# Planks_Rev2.net
KiCad netlist of a schematic drawn in EAGLE
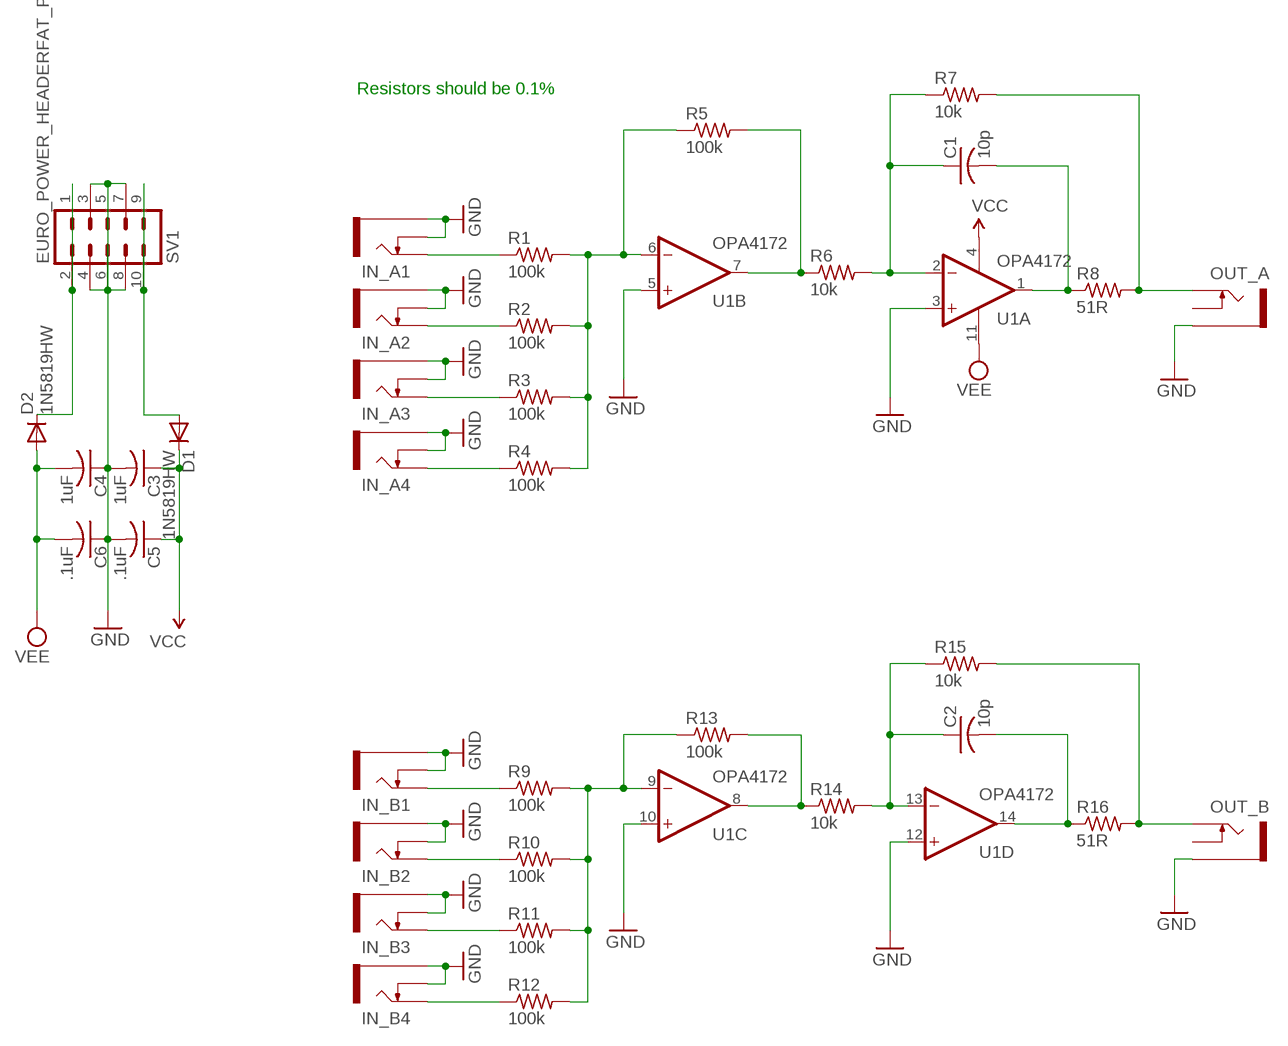
[diagram p0: schematic, sheet 1]

(export (version "E")
  (design (tool "Eeschema 10.0.6"))
  (components
    (comp (ref "C1")
      (value "10p")
      (footprint "eagle-import:C0603")
      (libsource (lib "eagle-import") (part "C-USC0603"))
    )
    (comp (ref "C2")
      (value "10p")
      (footprint "eagle-import:C0603")
      (libsource (lib "eagle-import") (part "C-USC0603"))
    )
    (comp (ref "C3")
      (value "1uF")
      (footprint "eagle-import:C0805")
      (libsource (lib "eagle-import") (part "C-USC0805"))
    )
    (comp (ref "C4")
      (value "1uF")
      (footprint "eagle-import:C0805")
      (libsource (lib "eagle-import") (part "C-USC0805"))
    )
    (comp (ref "C5")
      (value ".1uF")
      (footprint "eagle-import:C0603")
      (libsource (lib "eagle-import") (part "C-USC0603"))
    )
    (comp (ref "C6")
      (value ".1uF")
      (footprint "eagle-import:C0603")
      (libsource (lib "eagle-import") (part "C-USC0603"))
    )
    (comp (ref "D1")
      (value "1N5819HW")
      (footprint "eagle-import:SOD123")
      (libsource (lib "eagle-import") (part "DIODE-SOD123"))
    )
    (comp (ref "D2")
      (value "1N5819HW")
      (footprint "eagle-import:SOD123")
      (libsource (lib "eagle-import") (part "DIODE-SOD123"))
    )
    (comp (ref "IN_A1")
      (value "THONKICONNNEW")
      (footprint "eagle-import:WQP-PJ301M-12_JACK")
      (libsource (lib "eagle-import") (part "THONKICONNNEW"))
    )
    (comp (ref "IN_A2")
      (value "THONKICONNNEW")
      (footprint "eagle-import:WQP-PJ301M-12_JACK")
      (libsource (lib "eagle-import") (part "THONKICONNNEW"))
    )
    (comp (ref "IN_A3")
      (value "THONKICONNNEW")
      (footprint "eagle-import:WQP-PJ301M-12_JACK")
      (libsource (lib "eagle-import") (part "THONKICONNNEW"))
    )
    (comp (ref "IN_A4")
      (value "THONKICONNNEW")
      (footprint "eagle-import:WQP-PJ301M-12_JACK")
      (libsource (lib "eagle-import") (part "THONKICONNNEW"))
    )
    (comp (ref "IN_B1")
      (value "THONKICONNNEW")
      (footprint "eagle-import:WQP-PJ301M-12_JACK")
      (libsource (lib "eagle-import") (part "THONKICONNNEW"))
    )
    (comp (ref "IN_B2")
      (value "THONKICONNNEW")
      (footprint "eagle-import:WQP-PJ301M-12_JACK")
      (libsource (lib "eagle-import") (part "THONKICONNNEW"))
    )
    (comp (ref "IN_B3")
      (value "THONKICONNNEW")
      (footprint "eagle-import:WQP-PJ301M-12_JACK")
      (libsource (lib "eagle-import") (part "THONKICONNNEW"))
    )
    (comp (ref "IN_B4")
      (value "THONKICONNNEW")
      (footprint "eagle-import:WQP-PJ301M-12_JACK")
      (libsource (lib "eagle-import") (part "THONKICONNNEW"))
    )
    (comp (ref "OUT_A")
      (value "THONKICONNNEW")
      (footprint "eagle-import:WQP-PJ301M-12_JACK")
      (libsource (lib "eagle-import") (part "THONKICONNNEW"))
    )
    (comp (ref "OUT_B")
      (value "THONKICONNNEW")
      (footprint "eagle-import:WQP-PJ301M-12_JACK")
      (libsource (lib "eagle-import") (part "THONKICONNNEW"))
    )
    (comp (ref "R1")
      (value "100k")
      (footprint "eagle-import:R0603")
      (libsource (lib "eagle-import") (part "R-US_R0603"))
    )
    (comp (ref "R2")
      (value "100k")
      (footprint "eagle-import:R0603")
      (libsource (lib "eagle-import") (part "R-US_R0603"))
    )
    (comp (ref "R3")
      (value "100k")
      (footprint "eagle-import:R0603")
      (libsource (lib "eagle-import") (part "R-US_R0603"))
    )
    (comp (ref "R4")
      (value "100k")
      (footprint "eagle-import:R0603")
      (libsource (lib "eagle-import") (part "R-US_R0603"))
    )
    (comp (ref "R5")
      (value "100k")
      (footprint "eagle-import:R0603")
      (libsource (lib "eagle-import") (part "R-US_R0603"))
    )
    (comp (ref "R6")
      (value "10k")
      (footprint "eagle-import:R0603")
      (libsource (lib "eagle-import") (part "R-US_R0603"))
    )
    (comp (ref "R7")
      (value "10k")
      (footprint "eagle-import:R0603")
      (libsource (lib "eagle-import") (part "R-US_R0603"))
    )
    (comp (ref "R8")
      (value "51R")
      (footprint "eagle-import:R0603")
      (libsource (lib "eagle-import") (part "R-US_R0603"))
    )
    (comp (ref "R9")
      (value "100k")
      (footprint "eagle-import:R0603")
      (libsource (lib "eagle-import") (part "R-US_R0603"))
    )
    (comp (ref "R10")
      (value "100k")
      (footprint "eagle-import:R0603")
      (libsource (lib "eagle-import") (part "R-US_R0603"))
    )
    (comp (ref "R11")
      (value "100k")
      (footprint "eagle-import:R0603")
      (libsource (lib "eagle-import") (part "R-US_R0603"))
    )
    (comp (ref "R12")
      (value "100k")
      (footprint "eagle-import:R0603")
      (libsource (lib "eagle-import") (part "R-US_R0603"))
    )
    (comp (ref "R13")
      (value "100k")
      (footprint "eagle-import:R0603")
      (libsource (lib "eagle-import") (part "R-US_R0603"))
    )
    (comp (ref "R14")
      (value "10k")
      (footprint "eagle-import:R0603")
      (libsource (lib "eagle-import") (part "R-US_R0603"))
    )
    (comp (ref "R15")
      (value "10k")
      (footprint "eagle-import:R0603")
      (libsource (lib "eagle-import") (part "R-US_R0603"))
    )
    (comp (ref "R16")
      (value "51R")
      (footprint "eagle-import:R0603")
      (libsource (lib "eagle-import") (part "R-US_R0603"))
    )
    (comp (ref "SV1")
      (value "EURO_POWER_HEADERFAT_PADS")
      (footprint "eagle-import:EURO_PWR_HEADER_FAT")
      (libsource (lib "eagle-import") (part "EURO_POWER_HEADERFAT_PADS"))
    )
    (comp (ref "U1")
      (value "OPA4172")
      (footprint "eagle-import:SO14")
      (libsource (lib "eagle-import") (part "TL074_SMD"))
    )
  )
  (nets
    (net (code "1") (name "GND") (class "Default")
      (node (ref "C3") (pin "2") (pinfunction "2_2") (pintype "passive"))
      (node (ref "C4") (pin "1") (pinfunction "1_1") (pintype "passive"))
      (node (ref "C5") (pin "2") (pinfunction "2_2") (pintype "passive"))
      (node (ref "C6") (pin "1") (pinfunction "1_1") (pintype "passive"))
      (node (ref "IN_A1") (pin "P$2_SWITCH") (pinfunction "SWITCH_P$2_SWITCH") (pintype "passive"))
      (node (ref "IN_A1") (pin "P$3_SLEEVE") (pinfunction "SLEEVE_P$3_SLEEVE") (pintype "passive"))
      (node (ref "IN_A2") (pin "P$2_SWITCH") (pinfunction "SWITCH_P$2_SWITCH") (pintype "passive"))
      (node (ref "IN_A2") (pin "P$3_SLEEVE") (pinfunction "SLEEVE_P$3_SLEEVE") (pintype "passive"))
      (node (ref "IN_A3") (pin "P$2_SWITCH") (pinfunction "SWITCH_P$2_SWITCH") (pintype "passive"))
      (node (ref "IN_A3") (pin "P$3_SLEEVE") (pinfunction "SLEEVE_P$3_SLEEVE") (pintype "passive"))
      (node (ref "IN_A4") (pin "P$2_SWITCH") (pinfunction "SWITCH_P$2_SWITCH") (pintype "passive"))
      (node (ref "IN_A4") (pin "P$3_SLEEVE") (pinfunction "SLEEVE_P$3_SLEEVE") (pintype "passive"))
      (node (ref "IN_B1") (pin "P$2_SWITCH") (pinfunction "SWITCH_P$2_SWITCH") (pintype "passive"))
      (node (ref "IN_B1") (pin "P$3_SLEEVE") (pinfunction "SLEEVE_P$3_SLEEVE") (pintype "passive"))
      (node (ref "IN_B2") (pin "P$2_SWITCH") (pinfunction "SWITCH_P$2_SWITCH") (pintype "passive"))
      (node (ref "IN_B2") (pin "P$3_SLEEVE") (pinfunction "SLEEVE_P$3_SLEEVE") (pintype "passive"))
      (node (ref "IN_B3") (pin "P$2_SWITCH") (pinfunction "SWITCH_P$2_SWITCH") (pintype "passive"))
      (node (ref "IN_B3") (pin "P$3_SLEEVE") (pinfunction "SLEEVE_P$3_SLEEVE") (pintype "passive"))
      (node (ref "IN_B4") (pin "P$2_SWITCH") (pinfunction "SWITCH_P$2_SWITCH") (pintype "passive"))
      (node (ref "IN_B4") (pin "P$3_SLEEVE") (pinfunction "SLEEVE_P$3_SLEEVE") (pintype "passive"))
      (node (ref "OUT_A") (pin "P$3_SLEEVE") (pinfunction "SLEEVE_P$3_SLEEVE") (pintype "passive"))
      (node (ref "OUT_B") (pin "P$3_SLEEVE") (pinfunction "SLEEVE_P$3_SLEEVE") (pintype "passive"))
      (node (ref "SV1") (pin "3") (pinfunction "3_3") (pintype "passive"))
      (node (ref "SV1") (pin "4") (pinfunction "4_4") (pintype "passive"))
      (node (ref "SV1") (pin "5") (pinfunction "5_5") (pintype "passive"))
      (node (ref "SV1") (pin "6") (pinfunction "6_6") (pintype "passive"))
      (node (ref "SV1") (pin "7") (pinfunction "7_7") (pintype "passive"))
      (node (ref "SV1") (pin "8") (pinfunction "8_8") (pintype "passive"))
      (node (ref "U1") (pin "10") (pinfunction "+IN_10") (pintype "input"))
      (node (ref "U1") (pin "12") (pinfunction "+IN_12") (pintype "input"))
      (node (ref "U1") (pin "3") (pinfunction "+IN_3") (pintype "input"))
      (node (ref "U1") (pin "5") (pinfunction "+IN_5") (pintype "input"))
    )
    (net (code "2") (name "Net-(D1-PadA)") (class "Default")
      (node (ref "D1") (pin "A") (pinfunction "A_A") (pintype "passive"))
      (node (ref "SV1") (pin "10") (pinfunction "10_10") (pintype "passive"))
      (node (ref "SV1") (pin "9") (pinfunction "9_9") (pintype "passive"))
    )
    (net (code "3") (name "Net-(D2-PadC)") (class "Default")
      (node (ref "D2") (pin "C") (pinfunction "C_C") (pintype "passive"))
      (node (ref "SV1") (pin "1") (pinfunction "1_1") (pintype "passive"))
      (node (ref "SV1") (pin "2") (pinfunction "2_2") (pintype "passive"))
    )
    (net (code "4") (name "Net-(IN_A1-TIP)") (class "Default")
      (node (ref "IN_A1") (pin "P$1_TIP") (pinfunction "TIP_P$1_TIP") (pintype "passive"))
      (node (ref "R1") (pin "1") (pinfunction "1_1") (pintype "passive"))
    )
    (net (code "5") (name "Net-(IN_A2-TIP)") (class "Default")
      (node (ref "IN_A2") (pin "P$1_TIP") (pinfunction "TIP_P$1_TIP") (pintype "passive"))
      (node (ref "R2") (pin "1") (pinfunction "1_1") (pintype "passive"))
    )
    (net (code "6") (name "Net-(IN_A3-TIP)") (class "Default")
      (node (ref "IN_A3") (pin "P$1_TIP") (pinfunction "TIP_P$1_TIP") (pintype "passive"))
      (node (ref "R3") (pin "1") (pinfunction "1_1") (pintype "passive"))
    )
    (net (code "7") (name "Net-(IN_A4-TIP)") (class "Default")
      (node (ref "IN_A4") (pin "P$1_TIP") (pinfunction "TIP_P$1_TIP") (pintype "passive"))
      (node (ref "R4") (pin "1") (pinfunction "1_1") (pintype "passive"))
    )
    (net (code "8") (name "Net-(IN_B1-TIP)") (class "Default")
      (node (ref "IN_B1") (pin "P$1_TIP") (pinfunction "TIP_P$1_TIP") (pintype "passive"))
      (node (ref "R9") (pin "1") (pinfunction "1_1") (pintype "passive"))
    )
    (net (code "9") (name "Net-(IN_B2-TIP)") (class "Default")
      (node (ref "IN_B2") (pin "P$1_TIP") (pinfunction "TIP_P$1_TIP") (pintype "passive"))
      (node (ref "R10") (pin "1") (pinfunction "1_1") (pintype "passive"))
    )
    (net (code "10") (name "Net-(IN_B3-TIP)") (class "Default")
      (node (ref "IN_B3") (pin "P$1_TIP") (pinfunction "TIP_P$1_TIP") (pintype "passive"))
      (node (ref "R11") (pin "1") (pinfunction "1_1") (pintype "passive"))
    )
    (net (code "11") (name "Net-(IN_B4-TIP)") (class "Default")
      (node (ref "IN_B4") (pin "P$1_TIP") (pinfunction "TIP_P$1_TIP") (pintype "passive"))
      (node (ref "R12") (pin "1") (pinfunction "1_1") (pintype "passive"))
    )
    (net (code "12") (name "Net-(OUT_A-TIP)") (class "Default")
      (node (ref "OUT_A") (pin "P$1_TIP") (pinfunction "TIP_P$1_TIP") (pintype "passive"))
      (node (ref "R7") (pin "2") (pinfunction "2_2") (pintype "passive"))
      (node (ref "R8") (pin "2") (pinfunction "2_2") (pintype "passive"))
    )
    (net (code "13") (name "Net-(OUT_B-TIP)") (class "Default")
      (node (ref "OUT_B") (pin "P$1_TIP") (pinfunction "TIP_P$1_TIP") (pintype "passive"))
      (node (ref "R15") (pin "2") (pinfunction "2_2") (pintype "passive"))
      (node (ref "R16") (pin "2") (pinfunction "2_2") (pintype "passive"))
    )
    (net (code "14") (name "Net-(U1A--IN)") (class "Default")
      (node (ref "C1") (pin "1") (pinfunction "1_1") (pintype "passive"))
      (node (ref "R6") (pin "2") (pinfunction "2_2") (pintype "passive"))
      (node (ref "R7") (pin "1") (pinfunction "1_1") (pintype "passive"))
      (node (ref "U1") (pin "2") (pinfunction "-IN_2") (pintype "input"))
    )
    (net (code "15") (name "Net-(U1A-OUT)") (class "Default")
      (node (ref "C1") (pin "2") (pinfunction "2_2") (pintype "passive"))
      (node (ref "R8") (pin "1") (pinfunction "1_1") (pintype "passive"))
      (node (ref "U1") (pin "1") (pinfunction "OUT_1") (pintype "output"))
    )
    (net (code "16") (name "Net-(U1B--IN)") (class "Default")
      (node (ref "R1") (pin "2") (pinfunction "2_2") (pintype "passive"))
      (node (ref "R2") (pin "2") (pinfunction "2_2") (pintype "passive"))
      (node (ref "R3") (pin "2") (pinfunction "2_2") (pintype "passive"))
      (node (ref "R4") (pin "2") (pinfunction "2_2") (pintype "passive"))
      (node (ref "R5") (pin "1") (pinfunction "1_1") (pintype "passive"))
      (node (ref "U1") (pin "6") (pinfunction "-IN_6") (pintype "input"))
    )
    (net (code "17") (name "Net-(U1B-OUT)") (class "Default")
      (node (ref "R5") (pin "2") (pinfunction "2_2") (pintype "passive"))
      (node (ref "R6") (pin "1") (pinfunction "1_1") (pintype "passive"))
      (node (ref "U1") (pin "7") (pinfunction "OUT_7") (pintype "output"))
    )
    (net (code "18") (name "Net-(U1C--IN)") (class "Default")
      (node (ref "R10") (pin "2") (pinfunction "2_2") (pintype "passive"))
      (node (ref "R11") (pin "2") (pinfunction "2_2") (pintype "passive"))
      (node (ref "R12") (pin "2") (pinfunction "2_2") (pintype "passive"))
      (node (ref "R13") (pin "1") (pinfunction "1_1") (pintype "passive"))
      (node (ref "R9") (pin "2") (pinfunction "2_2") (pintype "passive"))
      (node (ref "U1") (pin "9") (pinfunction "-IN_9") (pintype "input"))
    )
    (net (code "19") (name "Net-(U1C-OUT)") (class "Default")
      (node (ref "R13") (pin "2") (pinfunction "2_2") (pintype "passive"))
      (node (ref "R14") (pin "1") (pinfunction "1_1") (pintype "passive"))
      (node (ref "U1") (pin "8") (pinfunction "OUT_8") (pintype "output"))
    )
    (net (code "20") (name "Net-(U1D--IN)") (class "Default")
      (node (ref "C2") (pin "1") (pinfunction "1_1") (pintype "passive"))
      (node (ref "R14") (pin "2") (pinfunction "2_2") (pintype "passive"))
      (node (ref "R15") (pin "1") (pinfunction "1_1") (pintype "passive"))
      (node (ref "U1") (pin "13") (pinfunction "-IN_13") (pintype "input"))
    )
    (net (code "21") (name "Net-(U1D-OUT)") (class "Default")
      (node (ref "C2") (pin "2") (pinfunction "2_2") (pintype "passive"))
      (node (ref "R16") (pin "1") (pinfunction "1_1") (pintype "passive"))
      (node (ref "U1") (pin "14") (pinfunction "OUT_14") (pintype "output"))
    )
    (net (code "22") (name "VCC") (class "Default")
      (node (ref "C3") (pin "1") (pinfunction "1_1") (pintype "passive"))
      (node (ref "C5") (pin "1") (pinfunction "1_1") (pintype "passive"))
      (node (ref "D1") (pin "C") (pinfunction "C_C") (pintype "passive"))
      (node (ref "U1") (pin "4") (pinfunction "V+_4") (pintype "power_in"))
    )
    (net (code "23") (name "VEE") (class "Default")
      (node (ref "C4") (pin "2") (pinfunction "2_2") (pintype "passive"))
      (node (ref "C6") (pin "2") (pinfunction "2_2") (pintype "passive"))
      (node (ref "D2") (pin "A") (pinfunction "A_A") (pintype "passive"))
      (node (ref "U1") (pin "11") (pinfunction "V-_11") (pintype "power_in"))
    )
    (net (code "24") (name "unconnected-(OUT_A-SWITCH-PadP$2_SWITCH)") (class "Default")
      (node (ref "OUT_A") (pin "P$2_SWITCH") (pinfunction "SWITCH_P$2_SWITCH") (pintype "passive"))
    )
    (net (code "25") (name "unconnected-(OUT_B-SWITCH-PadP$2_SWITCH)") (class "Default")
      (node (ref "OUT_B") (pin "P$2_SWITCH") (pinfunction "SWITCH_P$2_SWITCH") (pintype "passive"))
    )
  )
)
